# 1lab_vodoreziv_rs485.net
KiCad netlist of a schematic drawn in Altium Designer
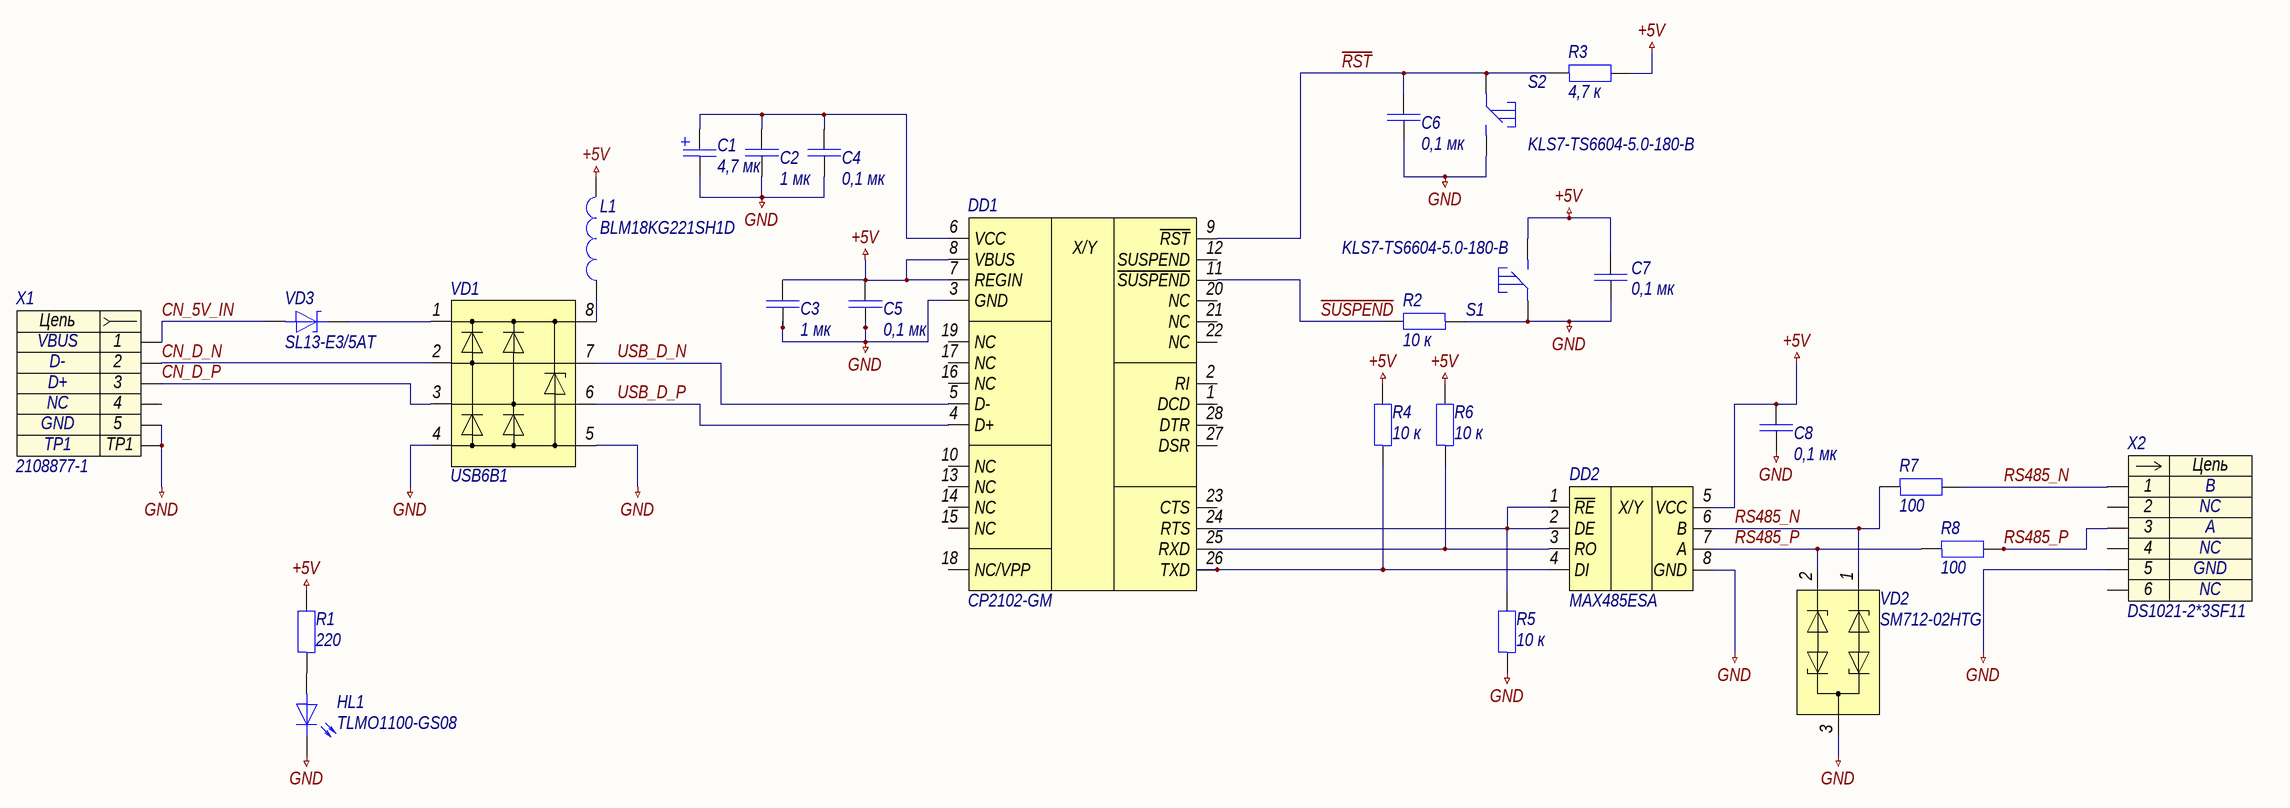
[diagram p0: 1lab_vodoreziv_rs485.SchDoc]

(export (version "E")
  (design (tool "Eeschema 10.0.6"))
  (components
    (comp (ref "C1")
      (value "4,7 мк")
      (footprint "C1206POLAR")
      (description "=Описание")
      (libsource (lib "Database_Students") (part "C-POLAR"))
    )
    (comp (ref "C2")
      (value "1 мк")
      (footprint "C0603")
      (description "=Описание")
      (libsource (lib "Database_Students") (part "C-NONPOLAR"))
    )
    (comp (ref "C3")
      (value "1 мк")
      (footprint "C0603")
      (description "=Описание")
      (libsource (lib "Database_Students") (part "C-NONPOLAR"))
    )
    (comp (ref "C4")
      (value "0,1 мк")
      (footprint "C0603")
      (description "=Описание")
      (libsource (lib "Database_Students") (part "C-NONPOLAR"))
    )
    (comp (ref "C5")
      (value "0,1 мк")
      (footprint "C0603")
      (description "=Описание")
      (libsource (lib "Database_Students") (part "C-NONPOLAR"))
    )
    (comp (ref "C6")
      (value "0,1 мк")
      (footprint "C0603")
      (description "=Описание")
      (libsource (lib "Database_Students") (part "C-NONPOLAR"))
    )
    (comp (ref "C7")
      (value "0,1 мк")
      (footprint "C0603")
      (description "=Описание")
      (libsource (lib "Database_Students") (part "C-NONPOLAR"))
    )
    (comp (ref "C8")
      (value "0,1 мк")
      (footprint "C0603")
      (description "=Описание")
      (libsource (lib "Database_Students") (part "C-NONPOLAR"))
    )
    (comp (ref "DD1")
      (value "CP2102-GM")
      (footprint "QFN-24")
      (description "=Описание")
      (libsource (lib "Database_Students") (part "CP2102-GM"))
    )
    (comp (ref "DD2")
      (value "MAX485ESA")
      (footprint "SOIC-8")
      (description "=Описание")
      (libsource (lib "Database_Students") (part "MAX485ESA"))
    )
    (comp (ref "HL1")
      (value "TLMO1100-GS08")
      (footprint "HL0603")
      (description "=Описание")
      (libsource (lib "Database_Students") (part "HL-COMMON"))
    )
    (comp (ref "L1")
      (value "BLM18KG221SH1D")
      (footprint "BLM-2-0603")
      (description "=Описание")
      (libsource (lib "Database_Students") (part "FERRITE-BEAD"))
    )
    (comp (ref "R1")
      (value "220")
      (footprint "R0603")
      (description "=Описание")
      (libsource (lib "Database_Students") (part "R-COMMON"))
    )
    (comp (ref "R2")
      (value "10 к")
      (footprint "R0603")
      (description "=Описание")
      (libsource (lib "Database_Students") (part "R-COMMON"))
    )
    (comp (ref "R3")
      (value "4,7 к")
      (footprint "R0603")
      (description "=Описание")
      (libsource (lib "Database_Students") (part "R-COMMON"))
    )
    (comp (ref "R4")
      (value "10 к")
      (footprint "R0603")
      (description "=Описание")
      (libsource (lib "Database_Students") (part "R-COMMON"))
    )
    (comp (ref "R5")
      (value "10 к")
      (footprint "R0603")
      (description "=Описание")
      (libsource (lib "Database_Students") (part "R-COMMON"))
    )
    (comp (ref "R6")
      (value "10 к")
      (footprint "R0603")
      (description "=Описание")
      (libsource (lib "Database_Students") (part "R-COMMON"))
    )
    (comp (ref "R7")
      (value "100")
      (footprint "R0603")
      (description "=Описание")
      (libsource (lib "Database_Students") (part "R-COMMON"))
    )
    (comp (ref "R8")
      (value "100")
      (footprint "R0603")
      (description "=Описание")
      (libsource (lib "Database_Students") (part "R-COMMON"))
    )
    (comp (ref "S1")
      (value "KLS7-TS6604-5.0-180-B")
      (footprint "KLS7-TS6604_500")
      (libsource (lib "button") (part "KLS7-TS6604-5.0-180-B"))
    )
    (comp (ref "S2")
      (value "KLS7-TS6604-5.0-180-B")
      (footprint "KLS7-TS6604_500")
      (libsource (lib "button") (part "KLS7-TS6604-5.0-180-B"))
    )
    (comp (ref "VD1")
      (value "USB6B1")
      (footprint "SO-8")
      (description "=Описание")
      (libsource (lib "Database_Students") (part "USB6B1"))
    )
    (comp (ref "VD2")
      (value "SM712-02HTG")
      (footprint "SOT23-3")
      (description "=Описание")
      (libsource (lib "Database_Students") (part "SM712-02HTG"))
    )
    (comp (ref "VD3")
      (value "SL13-E3/5AT")
      (footprint "DO-214AC")
      (description "=Описание")
      (libsource (lib "Database_Students") (part "DIODE-SCHOTTKY"))
    )
    (comp (ref "X1")
      (value "2108877-1")
      (footprint "2108877-1")
      (libsource (lib "Database_Students") (part "HEADER-5-TP1-SCT"))
    )
    (comp (ref "X2")
      (value "DS1021-2*3SF11")
      (footprint "DS1021-2X3SF11")
      (libsource (lib "Database_Students") (part "HEADER-6-PLG"))
    )
  )
  (nets
    (net (code "1") (name "+5V") (class "Default")
      (node (ref "C3") (pin "2") (pinfunction "2_2") (pintype "passive"))
      (node (ref "C5") (pin "2") (pinfunction "2_2") (pintype "passive"))
      (node (ref "C7") (pin "2") (pinfunction "2_2") (pintype "passive"))
      (node (ref "C8") (pin "1") (pinfunction "1_1") (pintype "passive"))
      (node (ref "DD1") (pin "7") (pinfunction "REGIN_7") (pintype "passive"))
      (node (ref "DD1") (pin "8") (pinfunction "VBUS_8") (pintype "passive"))
      (node (ref "DD2") (pin "5") (pinfunction "VCC_5") (pintype "passive"))
      (node (ref "L1") (pin "2") (pinfunction "2_2") (pintype "passive"))
      (node (ref "R1") (pin "2") (pinfunction "2_2") (pintype "passive"))
      (node (ref "R3") (pin "2") (pinfunction "2_2") (pintype "passive"))
      (node (ref "R4") (pin "2") (pinfunction "2_2") (pintype "passive"))
      (node (ref "R6") (pin "2") (pinfunction "2_2") (pintype "passive"))
      (node (ref "S1") (pin "2") (pinfunction "2_2") (pintype "passive"))
    )
    (net (code "2") (name "/CN_5V_IN") (class "Default")
      (node (ref "VD3") (pin "2") (pinfunction "2_2") (pintype "passive"))
      (node (ref "X1") (pin "1") (pinfunction "1_1") (pintype "passive"))
    )
    (net (code "3") (name "/CN_D_N") (class "Default")
      (node (ref "VD1") (pin "2") (pinfunction "2_2") (pintype "passive"))
      (node (ref "X1") (pin "2") (pinfunction "2_2") (pintype "passive"))
    )
    (net (code "4") (name "/CN_D_P") (class "Default")
      (node (ref "VD1") (pin "3") (pinfunction "3_3") (pintype "passive"))
      (node (ref "X1") (pin "3") (pinfunction "3_3") (pintype "passive"))
    )
    (net (code "5") (name "/RS485_N") (class "Default")
      (node (ref "DD2") (pin "6") (pinfunction "B_6") (pintype "passive"))
      (node (ref "R7") (pin "1") (pinfunction "1_1") (pintype "passive"))
      (node (ref "R7") (pin "2") (pinfunction "2_2") (pintype "passive"))
      (node (ref "VD2") (pin "1") (pinfunction "1_1") (pintype "passive"))
      (node (ref "X2") (pin "1") (pinfunction "1_1") (pintype "passive"))
    )
    (net (code "6") (name "/RS485_P") (class "Default")
      (node (ref "DD2") (pin "7") (pinfunction "A_7") (pintype "passive"))
      (node (ref "R8") (pin "1") (pinfunction "1_1") (pintype "passive"))
      (node (ref "R8") (pin "2") (pinfunction "2_2") (pintype "passive"))
      (node (ref "VD2") (pin "2") (pinfunction "2_2") (pintype "passive"))
      (node (ref "X2") (pin "3") (pinfunction "3_3") (pintype "passive"))
    )
    (net (code "7") (name "/USB_D_N") (class "Default")
      (node (ref "DD1") (pin "5") (pinfunction "D-_5") (pintype "passive"))
      (node (ref "VD1") (pin "7") (pinfunction "7_7") (pintype "passive"))
    )
    (net (code "8") (name "/USB_D_P") (class "Default")
      (node (ref "DD1") (pin "4") (pinfunction "D+_4") (pintype "passive"))
      (node (ref "VD1") (pin "6") (pinfunction "6_6") (pintype "passive"))
    )
    (net (code "9") (name "/~{RST}") (class "Default")
      (node (ref "C6") (pin "1") (pinfunction "1_1") (pintype "passive"))
      (node (ref "DD1") (pin "9") (pinfunction "~{RST}_9") (pintype "passive"))
      (node (ref "R3") (pin "1") (pinfunction "1_1") (pintype "passive"))
      (node (ref "S2") (pin "1") (pinfunction "1_1") (pintype "passive"))
    )
    (net (code "10") (name "/~{SUSPEND}") (class "Default")
      (node (ref "DD1") (pin "11") (pinfunction "~{SUSPEND}_11") (pintype "passive"))
      (node (ref "R2") (pin "2") (pinfunction "2_2") (pintype "passive"))
    )
    (net (code "11") (name "GND") (class "Default")
      (node (ref "C1") (pin "2") (pinfunction "2_2") (pintype "passive"))
      (node (ref "C2") (pin "2") (pinfunction "2_2") (pintype "passive"))
      (node (ref "C3") (pin "1") (pinfunction "1_1") (pintype "passive"))
      (node (ref "C4") (pin "2") (pinfunction "2_2") (pintype "passive"))
      (node (ref "C5") (pin "1") (pinfunction "1_1") (pintype "passive"))
      (node (ref "C6") (pin "2") (pinfunction "2_2") (pintype "passive"))
      (node (ref "C7") (pin "1") (pinfunction "1_1") (pintype "passive"))
      (node (ref "C8") (pin "2") (pinfunction "2_2") (pintype "passive"))
      (node (ref "DD1") (pin "3") (pinfunction "GND_3") (pintype "passive"))
      (node (ref "DD2") (pin "8") (pinfunction "GND_8") (pintype "passive"))
      (node (ref "HL1") (pin "1") (pinfunction "1_1") (pintype "passive"))
      (node (ref "R2") (pin "1") (pinfunction "1_1") (pintype "passive"))
      (node (ref "R5") (pin "1") (pinfunction "1_1") (pintype "passive"))
      (node (ref "S1") (pin "1") (pinfunction "1_1") (pintype "passive"))
      (node (ref "S2") (pin "2") (pinfunction "2_2") (pintype "passive"))
      (node (ref "VD1") (pin "4") (pinfunction "4_4") (pintype "passive"))
      (node (ref "VD1") (pin "5") (pinfunction "5_5") (pintype "passive"))
      (node (ref "VD2") (pin "3") (pinfunction "3_3") (pintype "passive"))
      (node (ref "X1") (pin "5") (pinfunction "5_5") (pintype "passive"))
      (node (ref "X1") (pin "TP1") (pinfunction "TP1_TP1") (pintype "passive"))
      (node (ref "X2") (pin "5") (pinfunction "5_5") (pintype "passive"))
    )
    (net (code "12") (name "Net-(DD1-RTS)") (class "Default")
      (node (ref "DD1") (pin "24") (pinfunction "RTS_24") (pintype "passive"))
      (node (ref "DD2") (pin "1") (pinfunction "~{RE}_1") (pintype "passive"))
      (node (ref "DD2") (pin "2") (pinfunction "DE_2") (pintype "passive"))
      (node (ref "R5") (pin "2") (pinfunction "2_2") (pintype "passive"))
    )
    (net (code "13") (name "Net-(DD1-RXD)") (class "Default")
      (node (ref "DD1") (pin "25") (pinfunction "RXD_25") (pintype "passive"))
      (node (ref "DD2") (pin "3") (pinfunction "RO_3") (pintype "passive"))
      (node (ref "R6") (pin "1") (pinfunction "1_1") (pintype "passive"))
    )
    (net (code "14") (name "Net-(DD1-TXD)") (class "Default")
      (node (ref "DD1") (pin "26") (pinfunction "TXD_26") (pintype "passive"))
      (node (ref "DD2") (pin "4") (pinfunction "DI_4") (pintype "passive"))
      (node (ref "R4") (pin "1") (pinfunction "1_1") (pintype "passive"))
    )
    (net (code "15") (name "Net-(DD1-VCC)") (class "Default")
      (node (ref "C1") (pin "1") (pinfunction "1_1") (pintype "passive"))
      (node (ref "C2") (pin "1") (pinfunction "1_1") (pintype "passive"))
      (node (ref "C4") (pin "1") (pinfunction "1_1") (pintype "passive"))
      (node (ref "DD1") (pin "6") (pinfunction "VCC_6") (pintype "passive"))
    )
    (net (code "16") (name "Net-(HL1-Pad2)") (class "Default")
      (node (ref "HL1") (pin "2") (pinfunction "2_2") (pintype "passive"))
      (node (ref "R1") (pin "1") (pinfunction "1_1") (pintype "passive"))
    )
    (net (code "17") (name "Net-(L1-Pad1)") (class "Default")
      (node (ref "L1") (pin "1") (pinfunction "1_1") (pintype "passive"))
      (node (ref "VD1") (pin "8") (pinfunction "8_8") (pintype "passive"))
    )
    (net (code "18") (name "Net-(VD1-Pad1)") (class "Default")
      (node (ref "VD1") (pin "1") (pinfunction "1_1") (pintype "passive"))
      (node (ref "VD3") (pin "1") (pinfunction "1_1") (pintype "passive"))
    )
    (net (code "19") (name "unconnected-(DD1-CTS-Pad23)") (class "Default")
      (node (ref "DD1") (pin "23") (pinfunction "CTS_23") (pintype "passive"))
    )
    (net (code "20") (name "unconnected-(DD1-DCD-Pad1)") (class "Default")
      (node (ref "DD1") (pin "1") (pinfunction "DCD_1") (pintype "passive"))
    )
    (net (code "21") (name "unconnected-(DD1-DSR-Pad27)") (class "Default")
      (node (ref "DD1") (pin "27") (pinfunction "DSR_27") (pintype "passive"))
    )
    (net (code "22") (name "unconnected-(DD1-DTR-Pad28)") (class "Default")
      (node (ref "DD1") (pin "28") (pinfunction "DTR_28") (pintype "passive"))
    )
    (net (code "23") (name "unconnected-(DD1-NC-Pad10)") (class "Default")
      (node (ref "DD1") (pin "10") (pinfunction "NC_10") (pintype "passive"))
    )
    (net (code "24") (name "unconnected-(DD1-NC-Pad13)") (class "Default")
      (node (ref "DD1") (pin "13") (pinfunction "NC_13") (pintype "passive"))
    )
    (net (code "25") (name "unconnected-(DD1-NC-Pad14)") (class "Default")
      (node (ref "DD1") (pin "14") (pinfunction "NC_14") (pintype "passive"))
    )
    (net (code "26") (name "unconnected-(DD1-NC-Pad15)") (class "Default")
      (node (ref "DD1") (pin "15") (pinfunction "NC_15") (pintype "passive"))
    )
    (net (code "27") (name "unconnected-(DD1-NC-Pad16)") (class "Default")
      (node (ref "DD1") (pin "16") (pinfunction "NC_16") (pintype "passive"))
    )
    (net (code "28") (name "unconnected-(DD1-NC-Pad17)") (class "Default")
      (node (ref "DD1") (pin "17") (pinfunction "NC_17") (pintype "passive"))
    )
    (net (code "29") (name "unconnected-(DD1-NC-Pad19)") (class "Default")
      (node (ref "DD1") (pin "19") (pinfunction "NC_19") (pintype "passive"))
    )
    (net (code "30") (name "unconnected-(DD1-NC-Pad20)") (class "Default")
      (node (ref "DD1") (pin "20") (pinfunction "NC_20") (pintype "passive"))
    )
    (net (code "31") (name "unconnected-(DD1-NC-Pad21)") (class "Default")
      (node (ref "DD1") (pin "21") (pinfunction "NC_21") (pintype "passive"))
    )
    (net (code "32") (name "unconnected-(DD1-NC-Pad22)") (class "Default")
      (node (ref "DD1") (pin "22") (pinfunction "NC_22") (pintype "passive"))
    )
    (net (code "33") (name "unconnected-(DD1-NC{slash}VPP-Pad18)") (class "Default")
      (node (ref "DD1") (pin "18") (pinfunction "NC/VPP_18") (pintype "passive"))
    )
    (net (code "34") (name "unconnected-(DD1-RI-Pad2)") (class "Default")
      (node (ref "DD1") (pin "2") (pinfunction "RI_2") (pintype "passive"))
    )
    (net (code "35") (name "unconnected-(DD1-SUSPEND-Pad12)") (class "Default")
      (node (ref "DD1") (pin "12") (pinfunction "SUSPEND_12") (pintype "passive"))
    )
    (net (code "36") (name "unconnected-(X1-Pad4)") (class "Default")
      (node (ref "X1") (pin "4") (pinfunction "4_4") (pintype "passive"))
    )
    (net (code "37") (name "unconnected-(X2-Pad2)") (class "Default")
      (node (ref "X2") (pin "2") (pinfunction "2_2") (pintype "passive"))
    )
    (net (code "38") (name "unconnected-(X2-Pad4)") (class "Default")
      (node (ref "X2") (pin "4") (pinfunction "4_4") (pintype "passive"))
    )
    (net (code "39") (name "unconnected-(X2-Pad6)") (class "Default")
      (node (ref "X2") (pin "6") (pinfunction "6_6") (pintype "passive"))
    )
  )
)
